# 1_1_6_Interface_board_Pressure_IMU.net
KiCad netlist of a schematic drawn in Altium Designer
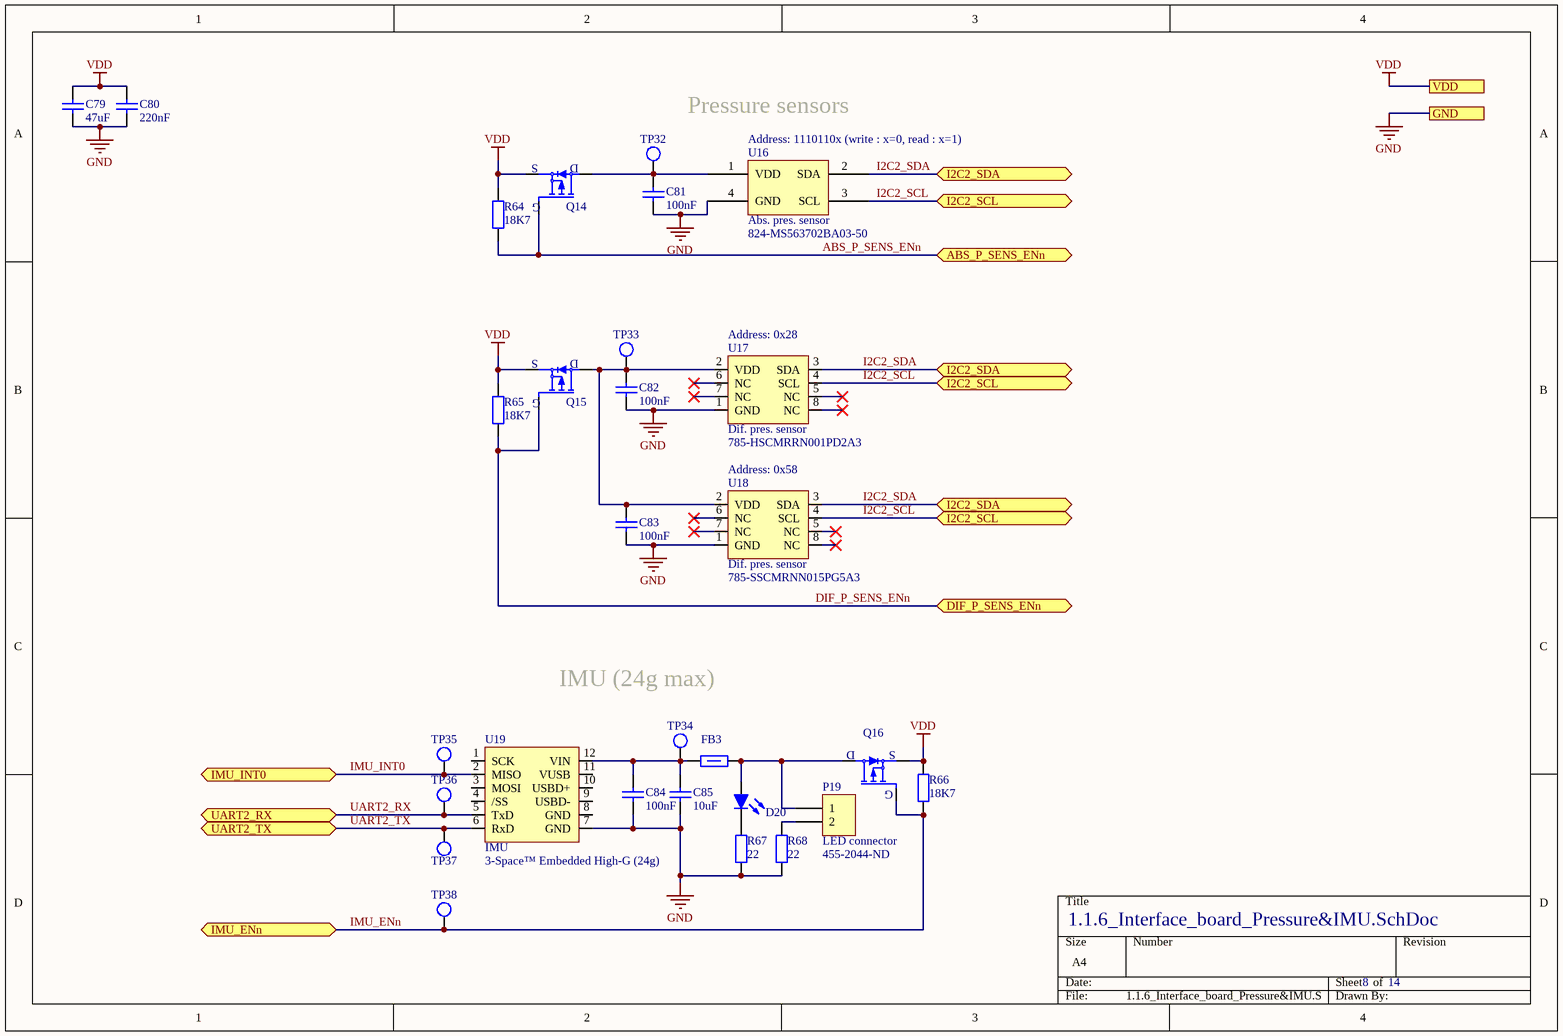
[diagram p0: 1.1.6_Interface_board_Pressure&IMU.SchDoc]

(export (version "E")
  (design (tool "Eeschema 10.0.6"))
  (components
    (comp (ref "C79")
      (value "47uF")
      (footprint "CAP1206W")
      (description "Capacitor")
      (libsource (lib "Rocket_library") (part "C_47uF_25v_1206"))
    )
    (comp (ref "C80")
      (value "220nF")
      (footprint "CAP0603R")
      (description "Capacitor")
      (libsource (lib "Rocket_library") (part "C_220nF"))
    )
    (comp (ref "C81")
      (value "100nF")
      (footprint "CAP0603R")
      (description "Capacitor")
      (libsource (lib "Rocket_library") (part "C_100nF"))
    )
    (comp (ref "C82")
      (value "100nF")
      (footprint "CAP0603R")
      (description "Capacitor")
      (libsource (lib "Rocket_library") (part "C_100nF"))
    )
    (comp (ref "C83")
      (value "100nF")
      (footprint "CAP0603R")
      (description "Capacitor")
      (libsource (lib "Rocket_library") (part "C_100nF"))
    )
    (comp (ref "C84")
      (value "100nF")
      (footprint "CAP0603R")
      (description "Capacitor")
      (libsource (lib "Rocket_library") (part "C_100nF"))
    )
    (comp (ref "C85")
      (value "10uF")
      (footprint "CAP0805W")
      (description "Capacitor")
      (libsource (lib "Rocket_library") (part "C_10uF_16v"))
    )
    (comp (ref "D20")
      (value "LED")
      (footprint "WL-SMCW")
      (description "Standard LEDs - SMD WL-SMCW Waterclr 0603 Green")
      (libsource (lib "Rocket_library") (part "LED_SMD_GREEN_0603"))
    )
    (comp (ref "FB3")
      (value "81-BLM18KG601SZ1D")
      (footprint "0603")
      (libsource (lib "Rocket_library") (part "Ferrite_bead"))
    )
    (comp (ref "P19")
      (value "LED connector")
      (footprint "CON_JST_XA_ S02B-XASS-1")
      (description "Header 2p JST XA 3A right angle")
      (fields (field (name "SUPPLIER PART NUMBER 1") "455-2044-ND"))
      (libsource (lib "Rocket_library") (part "Header 2p JST XA 3A right angle"))
    )
    (comp (ref "Q14")
      (value "MOSFET_P")
      (footprint "SOT23")
      (description "MOSFET 40V P-channel Trench MOSFET SOT-23-3")
      (libsource (lib "Rocket_library") (part "MOSFET_P_ 20V_1.5A"))
    )
    (comp (ref "Q15")
      (value "MOSFET_P")
      (footprint "SOT23")
      (description "MOSFET 40V P-channel Trench MOSFET SOT-23-3")
      (libsource (lib "Rocket_library") (part "MOSFET_P_ 20V_1.5A"))
    )
    (comp (ref "Q16")
      (value "MOSFET_P")
      (footprint "SOT23")
      (description "MOSFET 40V P-channel Trench MOSFET SOT-23-3")
      (libsource (lib "Rocket_library") (part "MOSFET_P_ 20V_1.5A"))
    )
    (comp (ref "R64")
      (value "18K7")
      (footprint "0603")
      (description "0.1W 18K7")
      (libsource (lib "Rocket_library") (part "R_0603_01W_18K7"))
    )
    (comp (ref "R65")
      (value "18K7")
      (footprint "0603")
      (description "0.1W 18K7")
      (libsource (lib "Rocket_library") (part "R_0603_01W_18K7"))
    )
    (comp (ref "R66")
      (value "18K7")
      (footprint "0603")
      (description "0.1W 18K7")
      (libsource (lib "Rocket_library") (part "R_0603_01W_18K7"))
    )
    (comp (ref "R67")
      (value "22")
      (footprint "0603")
      (description "0.25W 22Ohm")
      (libsource (lib "Rocket_library") (part "R_0603_025W_22Ohm"))
    )
    (comp (ref "R68")
      (value "22")
      (footprint "0603")
      (description "0.25W 22Ohm")
      (libsource (lib "Rocket_library") (part "R_0603_025W_22Ohm"))
    )
    (comp (ref "TP32")
      (value "Test point")
      (footprint "TP")
      (libsource (lib "Rocket_library") (part "Test point"))
    )
    (comp (ref "TP33")
      (value "Test point")
      (footprint "TP")
      (libsource (lib "Rocket_library") (part "Test point"))
    )
    (comp (ref "TP34")
      (value "Test point")
      (footprint "TP")
      (libsource (lib "Rocket_library") (part "Test point"))
    )
    (comp (ref "TP35")
      (value "Test point")
      (footprint "TP")
      (libsource (lib "Rocket_library") (part "Test point"))
    )
    (comp (ref "TP36")
      (value "Test point")
      (footprint "TP")
      (libsource (lib "Rocket_library") (part "Test point"))
    )
    (comp (ref "TP37")
      (value "Test point")
      (footprint "TP")
      (libsource (lib "Rocket_library") (part "Test point"))
    )
    (comp (ref "TP38")
      (value "Test point")
      (footprint "TP")
      (libsource (lib "Rocket_library") (part "Test point"))
    )
    (comp (ref "U16")
      (value "Abs. pres. sensor")
      (footprint "SMD_3.0X3.0MM_4P")
      (description "Pressure sensor")
      (fields (field (name "SUPPLIER PART NUMBER 1") "824-MS563702BA03-50"))
      (libsource (lib "Rocket_library") (part "MS563702BA03-50"))
    )
    (comp (ref "U17")
      (value "Dif. pres. sensor")
      (footprint "HSCMRRN060PDSA3")
      (description "Diff pressure sensor 1 psi")
      (fields (field (name "SUPPLIER PART NUMBER 1") "785-HSCMRRN001PD2A3"))
      (libsource (lib "Rocket_library") (part "HSCMRRN001PD2A3"))
    )
    (comp (ref "U18")
      (value "Dif. pres. sensor")
      (footprint "HSCMRRN060PDSA3")
      (description "Diff pressure sensor 0 psi to 15 psi")
      (fields (field (name "SUPPLIER PART NUMBER 1") "785-SSCMRNN015PG5A3"))
      (libsource (lib "Rocket_library") (part "SSCMRNN015PG5A3"))
    )
    (comp (ref "U19")
      (value "IMU")
      (footprint "Yost Labs 3-Spac Embedded")
      (fields (field (name "SUPPLIER PART NUMBER 1") "3-Space™ Embedded High-G (24g)"))
      (libsource (lib "Rocket_library") (part "YostLab_3-Space_Embedded"))
    )
  )
  (nets
    (net (code "1") (name "/ABS_P_SENS_ENn") (class "Default")
      (node (ref "Q14") (pin "1") (pinfunction "G_1") (pintype "passive"))
      (node (ref "R64") (pin "1") (pinfunction "1_1") (pintype "passive"))
    )
    (net (code "2") (name "/DIF_P_SENS_ENn") (class "Default")
      (node (ref "Q15") (pin "1") (pinfunction "G_1") (pintype "passive"))
      (node (ref "R65") (pin "1") (pinfunction "1_1") (pintype "passive"))
    )
    (net (code "3") (name "/I2C2_SCL") (class "Default")
      (node (ref "U16") (pin "3") (pinfunction "SCL_3") (pintype "passive"))
      (node (ref "U17") (pin "4") (pinfunction "SCL_4") (pintype "passive"))
      (node (ref "U18") (pin "4") (pinfunction "SCL_4") (pintype "passive"))
    )
    (net (code "4") (name "/I2C2_SDA") (class "Default")
      (node (ref "U16") (pin "2") (pinfunction "SDA_2") (pintype "passive"))
      (node (ref "U17") (pin "3") (pinfunction "SDA_3") (pintype "passive"))
      (node (ref "U18") (pin "3") (pinfunction "SDA_3") (pintype "passive"))
    )
    (net (code "5") (name "/IMU_ENn") (class "Default")
      (node (ref "Q16") (pin "1") (pinfunction "G_1") (pintype "passive"))
      (node (ref "R66") (pin "1") (pinfunction "1_1") (pintype "passive"))
      (node (ref "TP38") (pin "1") (pinfunction "1_1") (pintype "passive"))
    )
    (net (code "6") (name "/IMU_INT0") (class "Default")
      (node (ref "TP35") (pin "1") (pinfunction "1_1") (pintype "passive"))
      (node (ref "U19") (pin "2") (pinfunction "MISO_2") (pintype "passive"))
    )
    (net (code "7") (name "/UART2_RX") (class "Default")
      (node (ref "TP36") (pin "1") (pinfunction "1_1") (pintype "passive"))
      (node (ref "U19") (pin "5") (pinfunction "TxD_5") (pintype "passive"))
    )
    (net (code "8") (name "/UART2_TX") (class "Default")
      (node (ref "TP37") (pin "1") (pinfunction "1_1") (pintype "passive"))
      (node (ref "U19") (pin "6") (pinfunction "RxD_6") (pintype "passive"))
    )
    (net (code "9") (name "GND") (class "Default")
      (node (ref "C79") (pin "1") (pinfunction "1_1") (pintype "passive"))
      (node (ref "C80") (pin "1") (pinfunction "1_1") (pintype "passive"))
      (node (ref "C81") (pin "1") (pinfunction "1_1") (pintype "passive"))
      (node (ref "C82") (pin "1") (pinfunction "1_1") (pintype "passive"))
      (node (ref "C83") (pin "1") (pinfunction "1_1") (pintype "passive"))
      (node (ref "C84") (pin "1") (pinfunction "1_1") (pintype "passive"))
      (node (ref "C85") (pin "1") (pinfunction "1_1") (pintype "passive"))
      (node (ref "R67") (pin "1") (pinfunction "1_1") (pintype "passive"))
      (node (ref "R68") (pin "1") (pinfunction "1_1") (pintype "passive"))
      (node (ref "U16") (pin "4") (pinfunction "GND_4") (pintype "passive"))
      (node (ref "U17") (pin "1") (pinfunction "GND_1") (pintype "passive"))
      (node (ref "U18") (pin "1") (pinfunction "GND_1") (pintype "passive"))
      (node (ref "U19") (pin "7") (pinfunction "GND_7") (pintype "passive"))
    )
    (net (code "10") (name "Net-(D20-PadC)") (class "Default")
      (node (ref "D20") (pin "C") (pinfunction "C_C") (pintype "passive"))
      (node (ref "R67") (pin "2") (pinfunction "2_2") (pintype "passive"))
    )
    (net (code "11") (name "Net-(P19-Pad2)") (class "Default")
      (node (ref "P19") (pin "2") (pinfunction "2_2") (pintype "passive"))
      (node (ref "R68") (pin "2") (pinfunction "2_2") (pintype "passive"))
    )
    (net (code "12") (name "Net-(Q14-D)") (class "Default")
      (node (ref "C81") (pin "2") (pinfunction "2_2") (pintype "passive"))
      (node (ref "Q14") (pin "3") (pinfunction "D_3") (pintype "passive"))
      (node (ref "TP32") (pin "1") (pinfunction "1_1") (pintype "passive"))
      (node (ref "U16") (pin "1") (pinfunction "VDD_1") (pintype "passive"))
    )
    (net (code "13") (name "Net-(Q15-D)") (class "Default")
      (node (ref "C82") (pin "2") (pinfunction "2_2") (pintype "passive"))
      (node (ref "C83") (pin "2") (pinfunction "2_2") (pintype "passive"))
      (node (ref "Q15") (pin "3") (pinfunction "D_3") (pintype "passive"))
      (node (ref "TP33") (pin "1") (pinfunction "1_1") (pintype "passive"))
      (node (ref "U17") (pin "2") (pinfunction "VDD_2") (pintype "passive"))
      (node (ref "U18") (pin "2") (pinfunction "VDD_2") (pintype "passive"))
    )
    (net (code "14") (name "Net-(Q16-D)") (class "Default")
      (node (ref "D20") (pin "A") (pinfunction "A_A") (pintype "passive"))
      (node (ref "FB3") (pin "2") (pinfunction "2_2") (pintype "passive"))
      (node (ref "P19") (pin "1") (pinfunction "1_1") (pintype "passive"))
      (node (ref "Q16") (pin "3") (pinfunction "D_3") (pintype "passive"))
    )
    (net (code "15") (name "Net-(U19-VIN)") (class "Default")
      (node (ref "C84") (pin "2") (pinfunction "2_2") (pintype "passive"))
      (node (ref "C85") (pin "2") (pinfunction "2_2") (pintype "passive"))
      (node (ref "FB3") (pin "1") (pinfunction "1_1") (pintype "passive"))
      (node (ref "TP34") (pin "1") (pinfunction "1_1") (pintype "passive"))
      (node (ref "U19") (pin "12") (pinfunction "VIN_12") (pintype "passive"))
    )
    (net (code "16") (name "VDD") (class "Default")
      (node (ref "C79") (pin "2") (pinfunction "2_2") (pintype "passive"))
      (node (ref "C80") (pin "2") (pinfunction "2_2") (pintype "passive"))
      (node (ref "Q14") (pin "2") (pinfunction "S_2") (pintype "passive"))
      (node (ref "Q15") (pin "2") (pinfunction "S_2") (pintype "passive"))
      (node (ref "Q16") (pin "2") (pinfunction "S_2") (pintype "passive"))
      (node (ref "R64") (pin "2") (pinfunction "2_2") (pintype "passive"))
      (node (ref "R65") (pin "2") (pinfunction "2_2") (pintype "passive"))
      (node (ref "R66") (pin "2") (pinfunction "2_2") (pintype "passive"))
    )
    (net (code "17") (name "unconnected-(U17-NC-Pad5)") (class "Default")
      (node (ref "U17") (pin "5") (pinfunction "NC_5") (pintype "passive+no_connect"))
    )
    (net (code "18") (name "unconnected-(U17-NC-Pad6)") (class "Default")
      (node (ref "U17") (pin "6") (pinfunction "NC_6") (pintype "passive+no_connect"))
    )
    (net (code "19") (name "unconnected-(U17-NC-Pad7)") (class "Default")
      (node (ref "U17") (pin "7") (pinfunction "NC_7") (pintype "passive+no_connect"))
    )
    (net (code "20") (name "unconnected-(U17-NC-Pad8)") (class "Default")
      (node (ref "U17") (pin "8") (pinfunction "NC_8") (pintype "passive+no_connect"))
    )
    (net (code "21") (name "unconnected-(U18-NC-Pad5)") (class "Default")
      (node (ref "U18") (pin "5") (pinfunction "NC_5") (pintype "passive+no_connect"))
    )
    (net (code "22") (name "unconnected-(U18-NC-Pad6)") (class "Default")
      (node (ref "U18") (pin "6") (pinfunction "NC_6") (pintype "passive+no_connect"))
    )
    (net (code "23") (name "unconnected-(U18-NC-Pad7)") (class "Default")
      (node (ref "U18") (pin "7") (pinfunction "NC_7") (pintype "passive+no_connect"))
    )
    (net (code "24") (name "unconnected-(U18-NC-Pad8)") (class "Default")
      (node (ref "U18") (pin "8") (pinfunction "NC_8") (pintype "passive+no_connect"))
    )
    (net (code "25") (name "unconnected-(U19-GND-Pad8)") (class "Default")
      (node (ref "U19") (pin "8") (pinfunction "GND_8") (pintype "passive"))
    )
    (net (code "26") (name "unconnected-(U19-MOSI-Pad3)") (class "Default")
      (node (ref "U19") (pin "3") (pinfunction "MOSI_3") (pintype "passive"))
    )
    (net (code "27") (name "unconnected-(U19-SCK-Pad1)") (class "Default")
      (node (ref "U19") (pin "1") (pinfunction "SCK_1") (pintype "passive"))
    )
    (net (code "28") (name "unconnected-(U19-USBD+-Pad10)") (class "Default")
      (node (ref "U19") (pin "10") (pinfunction "USBD+_10") (pintype "passive"))
    )
    (net (code "29") (name "unconnected-(U19-USBD--Pad9)") (class "Default")
      (node (ref "U19") (pin "9") (pinfunction "USBD-_9") (pintype "passive"))
    )
    (net (code "30") (name "unconnected-(U19-VUSB-Pad11)") (class "Default")
      (node (ref "U19") (pin "11") (pinfunction "VUSB_11") (pintype "passive"))
    )
    (net (code "31") (name "unconnected-(U19-{slash}SS-Pad4)") (class "Default")
      (node (ref "U19") (pin "4") (pinfunction "/SS_4") (pintype "passive"))
    )
  )
)
